# Pyr0-Piezo_Direct-Extruder-FFC-Breakout_.net
KiCad netlist of a schematic drawn in EAGLE
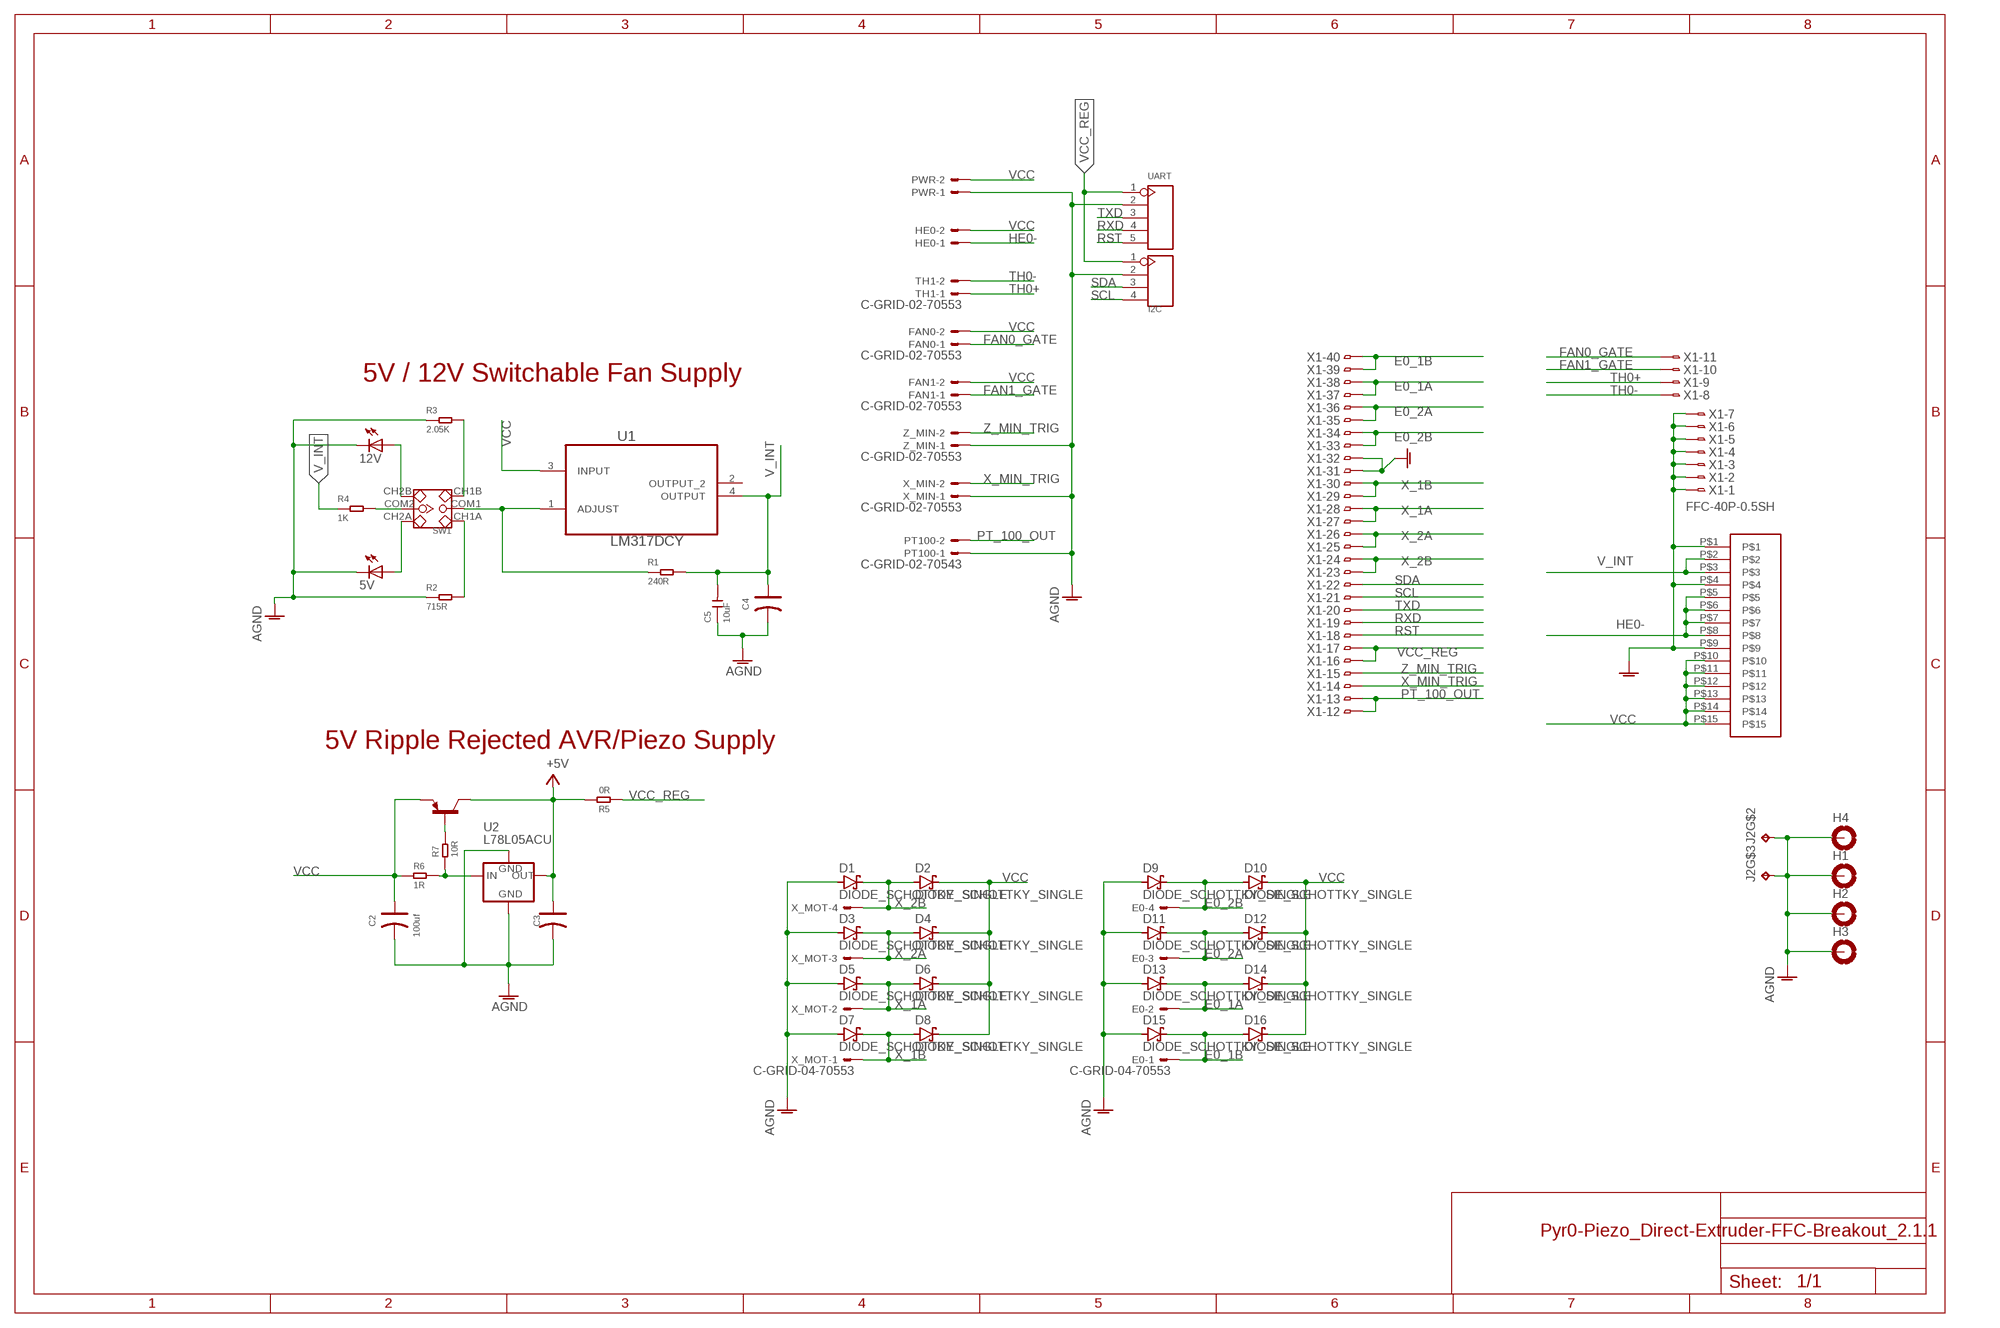
[diagram p0: schematic, sheet 1]

(export (version "E")
  (design (tool "Eeschema 10.0.6"))
  (components
    (comp (ref "5V")
      (value "LEDCHIP-LED0805")
      (footprint "eagle-import:CHIP-LED0805")
      (libsource (lib "eagle-import") (part "LEDCHIP-LED0805"))
    )
    (comp (ref "12V")
      (value "LEDCHIP-LED0805")
      (footprint "eagle-import:CHIP-LED0805")
      (libsource (lib "eagle-import") (part "LEDCHIP-LED0805"))
    )
    (comp (ref "C2")
      (value "100uf")
      (footprint "eagle-import:ALU-C-D5.3MM_LEFT")
      (fields (field (name "MPN") "KS 100uF/16V"))
      (libsource (lib "eagle-import") (part "DIP-ALUMINUM-100UF-16V(D5-H7MM)LEFT"))
    )
    (comp (ref "C3")
      (value "100uf")
      (footprint "eagle-import:ALU-C-D5.3MM_RIGHT")
      (libsource (lib "eagle-import") (part "DIP-ALUMINUM-100UF-16V(D5-H7MM)RIGHT"))
    )
    (comp (ref "C4")
      (value "100uf")
      (footprint "eagle-import:ALU-C-D5.3MM_RIGHT")
      (libsource (lib "eagle-import") (part "DIP-ALUMINUM-100UF-16V(D5-H7MM)RIGHT"))
    )
    (comp (ref "C5")
      (value "10uF")
      (footprint "eagle-import:CAPC2012X130")
      (libsource (lib "eagle-import") (part "SEEED-CAPACITOR_CERAMIC-10UF-25V-10%-X5R(0805)CAP_0805-3D"))
    )
    (comp (ref "D1")
      (value "DIODE_SCHOTTKY_SINGLE")
      (footprint "eagle-import:DO-214AC")
      (libsource (lib "eagle-import") (part "DIODE_SCHOTTKY_SINGLE"))
    )
    (comp (ref "D2")
      (value "DIODE_SCHOTTKY_SINGLE")
      (footprint "eagle-import:DO-214AC")
      (libsource (lib "eagle-import") (part "DIODE_SCHOTTKY_SINGLE"))
    )
    (comp (ref "D3")
      (value "DIODE_SCHOTTKY_SINGLE")
      (footprint "eagle-import:DO-214AC")
      (libsource (lib "eagle-import") (part "DIODE_SCHOTTKY_SINGLE"))
    )
    (comp (ref "D4")
      (value "DIODE_SCHOTTKY_SINGLE")
      (footprint "eagle-import:DO-214AC")
      (libsource (lib "eagle-import") (part "DIODE_SCHOTTKY_SINGLE"))
    )
    (comp (ref "D5")
      (value "DIODE_SCHOTTKY_SINGLE")
      (footprint "eagle-import:DO-214AC")
      (libsource (lib "eagle-import") (part "DIODE_SCHOTTKY_SINGLE"))
    )
    (comp (ref "D6")
      (value "DIODE_SCHOTTKY_SINGLE")
      (footprint "eagle-import:DO-214AC")
      (libsource (lib "eagle-import") (part "DIODE_SCHOTTKY_SINGLE"))
    )
    (comp (ref "D7")
      (value "DIODE_SCHOTTKY_SINGLE")
      (footprint "eagle-import:DO-214AC")
      (libsource (lib "eagle-import") (part "DIODE_SCHOTTKY_SINGLE"))
    )
    (comp (ref "D8")
      (value "DIODE_SCHOTTKY_SINGLE")
      (footprint "eagle-import:DO-214AC")
      (libsource (lib "eagle-import") (part "DIODE_SCHOTTKY_SINGLE"))
    )
    (comp (ref "D9")
      (value "DIODE_SCHOTTKY_SINGLE")
      (footprint "eagle-import:DO-214AC")
      (libsource (lib "eagle-import") (part "DIODE_SCHOTTKY_SINGLE"))
    )
    (comp (ref "D10")
      (value "DIODE_SCHOTTKY_SINGLE")
      (footprint "eagle-import:DO-214AC")
      (libsource (lib "eagle-import") (part "DIODE_SCHOTTKY_SINGLE"))
    )
    (comp (ref "D11")
      (value "DIODE_SCHOTTKY_SINGLE")
      (footprint "eagle-import:DO-214AC")
      (libsource (lib "eagle-import") (part "DIODE_SCHOTTKY_SINGLE"))
    )
    (comp (ref "D12")
      (value "DIODE_SCHOTTKY_SINGLE")
      (footprint "eagle-import:DO-214AC")
      (libsource (lib "eagle-import") (part "DIODE_SCHOTTKY_SINGLE"))
    )
    (comp (ref "D13")
      (value "DIODE_SCHOTTKY_SINGLE")
      (footprint "eagle-import:DO-214AC")
      (libsource (lib "eagle-import") (part "DIODE_SCHOTTKY_SINGLE"))
    )
    (comp (ref "D14")
      (value "DIODE_SCHOTTKY_SINGLE")
      (footprint "eagle-import:DO-214AC")
      (libsource (lib "eagle-import") (part "DIODE_SCHOTTKY_SINGLE"))
    )
    (comp (ref "D15")
      (value "DIODE_SCHOTTKY_SINGLE")
      (footprint "eagle-import:DO-214AC")
      (libsource (lib "eagle-import") (part "DIODE_SCHOTTKY_SINGLE"))
    )
    (comp (ref "D16")
      (value "DIODE_SCHOTTKY_SINGLE")
      (footprint "eagle-import:DO-214AC")
      (libsource (lib "eagle-import") (part "DIODE_SCHOTTKY_SINGLE"))
    )
    (comp (ref "E0")
      (value "C-GRID-04-70553")
      (footprint "eagle-import:70553-04")
      (fields (field (name "MF") "MOLEX"))
      (libsource (lib "eagle-import") (part "C-GRID-04-70553"))
    )
    (comp (ref "FAN0")
      (value "C-GRID-02-70553")
      (footprint "eagle-import:70553-02")
      (fields (field (name "MF") "MOLEX"))
      (libsource (lib "eagle-import") (part "C-GRID-02-70553"))
    )
    (comp (ref "FAN1")
      (value "C-GRID-02-70553")
      (footprint "eagle-import:70553-02")
      (fields (field (name "MF") "MOLEX"))
      (libsource (lib "eagle-import") (part "C-GRID-02-70553"))
    )
    (comp (ref "H1")
      (value "HOLES_MOUNT-PAD-ROUND3.2")
      (footprint "eagle-import:HOLES_3,2-PAD")
      (libsource (lib "eagle-import") (part "HOLES_MOUNT-PAD-ROUND3.2"))
    )
    (comp (ref "H2")
      (value "HOLES_MOUNT-PAD-ROUND3.2")
      (footprint "eagle-import:HOLES_3,2-PAD")
      (libsource (lib "eagle-import") (part "HOLES_MOUNT-PAD-ROUND3.2"))
    )
    (comp (ref "H3")
      (value "HOLES_MOUNT-PAD-ROUND3.2")
      (footprint "eagle-import:HOLES_3,2-PAD")
      (libsource (lib "eagle-import") (part "HOLES_MOUNT-PAD-ROUND3.2"))
    )
    (comp (ref "H4")
      (value "HOLES_MOUNT-PAD-ROUND3.2")
      (footprint "eagle-import:HOLES_3,2-PAD")
      (libsource (lib "eagle-import") (part "HOLES_MOUNT-PAD-ROUND3.2"))
    )
    (comp (ref "HE0")
      (value "KK-156-2")
      (footprint "eagle-import:KK-156-2")
      (fields (field (name "MF") "MOLEX"))
      (libsource (lib "eagle-import") (part "KK-156-2"))
    )
    (comp (ref "I2C")
      (value "SEEED-CONNECTOR_DIP-BLACK-FEMALE-HEADER-VERT(4P-2.54)JST-2.54MM_4P")
      (footprint "eagle-import:HDRVR4W64P254_1X4_1016X254X575B")
      (libsource (lib "eagle-import") (part "SEEED-CONNECTOR_DIP-BLACK-FEMALE-HEADER-VERT(4P-2.54)JST-2.54MM_4P"))
    )
    (comp (ref "J2")
      (value "FFC-15P-1MM")
      (footprint "eagle-import:FFC-15P-1MM")
      (libsource (lib "eagle-import") (part "FFC-15P-1MM"))
    )
    (comp (ref "PT100")
      (value "C-GRID-02-70543")
      (footprint "eagle-import:70543-02")
      (fields (field (name "MF") "MOLEX"))
      (libsource (lib "eagle-import") (part "C-GRID-02-70543"))
    )
    (comp (ref "PWR")
      (value "KK-156-2")
      (footprint "eagle-import:KK-156-2")
      (fields (field (name "MF") "MOLEX"))
      (libsource (lib "eagle-import") (part "KK-156-2"))
    )
    (comp (ref "Q2")
      (value "MMBT2907ALT1-PNP-SOT23-BEC")
      (footprint "eagle-import:SOT23-BEC")
      (libsource (lib "eagle-import") (part "-PNP-SOT23-BECMMBT2907ALT1"))
    )
    (comp (ref "R1")
      (value "240R")
      (footprint "eagle-import:SEEED-RESISTOR_R0603")
      (libsource (lib "eagle-import") (part "SEEED-RESISTOR_SMD-RES-1.5K-1%-1/10W(0603)DETAILED_MODEL"))
    )
    (comp (ref "R2")
      (value "715R")
      (footprint "eagle-import:SEEED-RESISTOR_R0603")
      (libsource (lib "eagle-import") (part "SEEED-RESISTOR_SMD-RES-1.5K-1%-1/10W(0603)DETAILED_MODEL"))
    )
    (comp (ref "R3")
      (value "2.05K")
      (footprint "eagle-import:SEEED-RESISTOR_R0603")
      (libsource (lib "eagle-import") (part "SEEED-RESISTOR_SMD-RES-1.5K-1%-1/10W(0603)DETAILED_MODEL"))
    )
    (comp (ref "R4")
      (value "1K")
      (footprint "eagle-import:SEEED-RESISTOR_R0603")
      (libsource (lib "eagle-import") (part "SEEED-RESISTOR_SMD-RES-1.5K-1%-1/10W(0603)DETAILED_MODEL"))
    )
    (comp (ref "R5")
      (value "0R")
      (footprint "eagle-import:R0805")
      (fields (field (name "MPN") "RC0805JR-072KL"))
      (libsource (lib "eagle-import") (part "SMD-RES-2K-5%-1/8W(0805)"))
    )
    (comp (ref "R6")
      (value "1R")
      (footprint "eagle-import:R0805")
      (fields (field (name "MPN") "RC0805JR-072KL"))
      (libsource (lib "eagle-import") (part "SMD-RES-2K-5%-1/8W(0805)"))
    )
    (comp (ref "R7")
      (value "10R")
      (footprint "eagle-import:R0805")
      (fields (field (name "MPN") "RC0805JR-072KL"))
      (libsource (lib "eagle-import") (part "SMD-RES-2K-5%-1/8W(0805)"))
    )
    (comp (ref "SW1")
      (value "SEEED-SWITCH_DIP-TOGGLE-SWITCH-2CH-(2X3P-2.54)DPDT_254_6P_UPDATE")
      (footprint "eagle-import:SEEED-SWITCH_SW6-2.54-9.0X3.5X3.2+2.0MM")
      (libsource (lib "eagle-import") (part "SEEED-SWITCH_DIP-TOGGLE-SWITCH-2CH-(2X3P-2.54)DPDT_254_6P_UPDATE"))
    )
    (comp (ref "TH1")
      (value "C-GRID-02-70553")
      (footprint "eagle-import:70553-02")
      (fields (field (name "MF") "MOLEX"))
      (libsource (lib "eagle-import") (part "C-GRID-02-70553"))
    )
    (comp (ref "U1")
      (value "LM317DCY")
      (footprint "eagle-import:SOT230P700X180-4N")
      (fields (field (name "MF") "Texas Instruments"))
      (libsource (lib "eagle-import") (part "LM317DCY"))
    )
    (comp (ref "U2")
      (value "L78L05ACU")
      (footprint "eagle-import:SOT89")
      (fields (field (name "MF") "STMicroelectronics") (field (name "MP") "L78L05ACU-TR"))
      (libsource (lib "eagle-import") (part "L78L05ACU"))
    )
    (comp (ref "UART")
      (value "JST-2.54MM_5P-2.54JST_2.54MM_5P_F")
      (footprint "eagle-import:HDRVR5W64P254_1X5_1270X254X575B")
      (libsource (lib "eagle-import") (part "JST-2.54MM_5P-2.54JST_2.54MM_5P_F"))
    )
    (comp (ref "X1")
      (value "FFC-40P-0.5SH")
      (footprint "eagle-import:FH12-40S-0.5SH")
      (fields (field (name "MPN") "FH12-40S-0.5SH(55)"))
      (libsource (lib "eagle-import") (part "FFC-40P-0.5SH"))
    )
    (comp (ref "X_MIN")
      (value "C-GRID-02-70553")
      (footprint "eagle-import:70553-02")
      (fields (field (name "MF") "MOLEX"))
      (libsource (lib "eagle-import") (part "C-GRID-02-70553"))
    )
    (comp (ref "X_MOT")
      (value "C-GRID-04-70553")
      (footprint "eagle-import:70553-04")
      (fields (field (name "MF") "MOLEX"))
      (libsource (lib "eagle-import") (part "C-GRID-04-70553"))
    )
    (comp (ref "Z_MIN")
      (value "C-GRID-02-70553")
      (footprint "eagle-import:70553-02")
      (fields (field (name "MF") "MOLEX"))
      (libsource (lib "eagle-import") (part "C-GRID-02-70553"))
    )
  )
  (nets
    (net (code "1") (name "+5V") (class "Default")
      (node (ref "C3") (pin "+") (pinfunction "+_+") (pintype "passive"))
      (node (ref "Q2") (pin "C") (pinfunction "C_C") (pintype "passive"))
      (node (ref "R5") (pin "2") (pinfunction "2_2") (pintype "passive"))
      (node (ref "U2") (pin "1") (pinfunction "OUT_1") (pintype "output"))
    )
    (net (code "2") (name "/E0_1A") (class "Default")
      (node (ref "D13") (pin "C") (pinfunction "C_C") (pintype "passive"))
      (node (ref "D14") (pin "A") (pinfunction "A_A") (pintype "passive"))
      (node (ref "E0") (pin "2") (pinfunction "S_2") (pintype "passive"))
      (node (ref "X1") (pin "37") (pinfunction "1_37") (pintype "passive"))
      (node (ref "X1") (pin "38") (pinfunction "1_38") (pintype "passive"))
    )
    (net (code "3") (name "/E0_1B") (class "Default")
      (node (ref "D15") (pin "C") (pinfunction "C_C") (pintype "passive"))
      (node (ref "D16") (pin "A") (pinfunction "A_A") (pintype "passive"))
      (node (ref "E0") (pin "1") (pinfunction "S_1") (pintype "passive"))
      (node (ref "X1") (pin "39") (pinfunction "1_39") (pintype "passive"))
      (node (ref "X1") (pin "40") (pinfunction "1_40") (pintype "passive"))
    )
    (net (code "4") (name "/E0_2A") (class "Default")
      (node (ref "D11") (pin "C") (pinfunction "C_C") (pintype "passive"))
      (node (ref "D12") (pin "A") (pinfunction "A_A") (pintype "passive"))
      (node (ref "E0") (pin "3") (pinfunction "S_3") (pintype "passive"))
      (node (ref "X1") (pin "35") (pinfunction "1_35") (pintype "passive"))
      (node (ref "X1") (pin "36") (pinfunction "1_36") (pintype "passive"))
    )
    (net (code "5") (name "/E0_2B") (class "Default")
      (node (ref "D10") (pin "A") (pinfunction "A_A") (pintype "passive"))
      (node (ref "D9") (pin "C") (pinfunction "C_C") (pintype "passive"))
      (node (ref "E0") (pin "4") (pinfunction "S_4") (pintype "passive"))
      (node (ref "X1") (pin "33") (pinfunction "1_33") (pintype "passive"))
      (node (ref "X1") (pin "34") (pinfunction "1_34") (pintype "passive"))
    )
    (net (code "6") (name "/FAN0_GATE") (class "Default")
      (node (ref "FAN0") (pin "1") (pinfunction "S_1") (pintype "passive"))
      (node (ref "X1") (pin "11") (pinfunction "1_11") (pintype "passive"))
    )
    (net (code "7") (name "/FAN1_GATE") (class "Default")
      (node (ref "FAN1") (pin "1") (pinfunction "S_1") (pintype "passive"))
      (node (ref "X1") (pin "10") (pinfunction "1_10") (pintype "passive"))
    )
    (net (code "8") (name "/HE0-") (class "Default")
      (node (ref "HE0") (pin "1") (pinfunction "S_1") (pintype "passive"))
      (node (ref "J2") (pin "P$5") (pinfunction "P$5_P$5") (pintype "bidirectional"))
      (node (ref "J2") (pin "P$6") (pinfunction "P$6_P$6") (pintype "bidirectional"))
      (node (ref "J2") (pin "P$7") (pinfunction "P$7_P$7") (pintype "bidirectional"))
      (node (ref "J2") (pin "P$8") (pinfunction "P$8_P$8") (pintype "bidirectional"))
    )
    (net (code "9") (name "/PT_100_OUT") (class "Default")
      (node (ref "PT100") (pin "2") (pinfunction "S_2") (pintype "passive"))
      (node (ref "X1") (pin "12") (pinfunction "1_12") (pintype "passive"))
      (node (ref "X1") (pin "13") (pinfunction "1_13") (pintype "passive"))
    )
    (net (code "10") (name "/RST") (class "Default")
      (node (ref "UART") (pin "5") (pinfunction "P$5_5") (pintype "bidirectional"))
      (node (ref "X1") (pin "18") (pinfunction "1_18") (pintype "passive"))
    )
    (net (code "11") (name "/RXD") (class "Default")
      (node (ref "UART") (pin "4") (pinfunction "P$4_4") (pintype "bidirectional"))
      (node (ref "X1") (pin "19") (pinfunction "1_19") (pintype "passive"))
    )
    (net (code "12") (name "/SCL") (class "Default")
      (node (ref "I2C") (pin "4") (pinfunction "P$4_4") (pintype "bidirectional"))
      (node (ref "X1") (pin "21") (pinfunction "1_21") (pintype "passive"))
    )
    (net (code "13") (name "/SDA") (class "Default")
      (node (ref "I2C") (pin "3") (pinfunction "P$3_3") (pintype "bidirectional"))
      (node (ref "X1") (pin "22") (pinfunction "1_22") (pintype "passive"))
    )
    (net (code "14") (name "/TH0+") (class "Default")
      (node (ref "TH1") (pin "1") (pinfunction "S_1") (pintype "passive"))
      (node (ref "X1") (pin "9") (pinfunction "1_9") (pintype "passive"))
    )
    (net (code "15") (name "/TH0-") (class "Default")
      (node (ref "TH1") (pin "2") (pinfunction "S_2") (pintype "passive"))
      (node (ref "X1") (pin "8") (pinfunction "1_8") (pintype "passive"))
    )
    (net (code "16") (name "/TXD") (class "Default")
      (node (ref "UART") (pin "3") (pinfunction "P$3_3") (pintype "bidirectional"))
      (node (ref "X1") (pin "20") (pinfunction "1_20") (pintype "passive"))
    )
    (net (code "17") (name "/VCC") (class "Default")
      (node (ref "C2") (pin "+") (pinfunction "+_+") (pintype "passive"))
      (node (ref "D10") (pin "C") (pinfunction "C_C") (pintype "passive"))
      (node (ref "D12") (pin "C") (pinfunction "C_C") (pintype "passive"))
      (node (ref "D14") (pin "C") (pinfunction "C_C") (pintype "passive"))
      (node (ref "D16") (pin "C") (pinfunction "C_C") (pintype "passive"))
      (node (ref "D2") (pin "C") (pinfunction "C_C") (pintype "passive"))
      (node (ref "D4") (pin "C") (pinfunction "C_C") (pintype "passive"))
      (node (ref "D6") (pin "C") (pinfunction "C_C") (pintype "passive"))
      (node (ref "D8") (pin "C") (pinfunction "C_C") (pintype "passive"))
      (node (ref "FAN0") (pin "2") (pinfunction "S_2") (pintype "passive"))
      (node (ref "FAN1") (pin "2") (pinfunction "S_2") (pintype "passive"))
      (node (ref "HE0") (pin "2") (pinfunction "S_2") (pintype "passive"))
      (node (ref "J2") (pin "P$10") (pinfunction "P$10_P$10") (pintype "bidirectional"))
      (node (ref "J2") (pin "P$11") (pinfunction "P$11_P$11") (pintype "bidirectional"))
      (node (ref "J2") (pin "P$12") (pinfunction "P$12_P$12") (pintype "bidirectional"))
      (node (ref "J2") (pin "P$13") (pinfunction "P$13_P$13") (pintype "bidirectional"))
      (node (ref "J2") (pin "P$14") (pinfunction "P$14_P$14") (pintype "bidirectional"))
      (node (ref "J2") (pin "P$15") (pinfunction "P$15_P$15") (pintype "bidirectional"))
      (node (ref "PWR") (pin "2") (pinfunction "S_2") (pintype "passive"))
      (node (ref "Q2") (pin "E") (pinfunction "E_E") (pintype "passive"))
      (node (ref "R6") (pin "1") (pinfunction "1_1") (pintype "passive"))
      (node (ref "U1") (pin "3") (pinfunction "INPUT_3") (pintype "input"))
    )
    (net (code "18") (name "/X_1A") (class "Default")
      (node (ref "D5") (pin "C") (pinfunction "C_C") (pintype "passive"))
      (node (ref "D6") (pin "A") (pinfunction "A_A") (pintype "passive"))
      (node (ref "X1") (pin "27") (pinfunction "1_27") (pintype "passive"))
      (node (ref "X1") (pin "28") (pinfunction "1_28") (pintype "passive"))
      (node (ref "X_MOT") (pin "2") (pinfunction "S_2") (pintype "passive"))
    )
    (net (code "19") (name "/X_1B") (class "Default")
      (node (ref "D7") (pin "C") (pinfunction "C_C") (pintype "passive"))
      (node (ref "D8") (pin "A") (pinfunction "A_A") (pintype "passive"))
      (node (ref "X1") (pin "29") (pinfunction "1_29") (pintype "passive"))
      (node (ref "X1") (pin "30") (pinfunction "1_30") (pintype "passive"))
      (node (ref "X_MOT") (pin "1") (pinfunction "S_1") (pintype "passive"))
    )
    (net (code "20") (name "/X_2A") (class "Default")
      (node (ref "D3") (pin "C") (pinfunction "C_C") (pintype "passive"))
      (node (ref "D4") (pin "A") (pinfunction "A_A") (pintype "passive"))
      (node (ref "X1") (pin "25") (pinfunction "1_25") (pintype "passive"))
      (node (ref "X1") (pin "26") (pinfunction "1_26") (pintype "passive"))
      (node (ref "X_MOT") (pin "3") (pinfunction "S_3") (pintype "passive"))
    )
    (net (code "21") (name "/X_2B") (class "Default")
      (node (ref "D1") (pin "C") (pinfunction "C_C") (pintype "passive"))
      (node (ref "D2") (pin "A") (pinfunction "A_A") (pintype "passive"))
      (node (ref "X1") (pin "23") (pinfunction "1_23") (pintype "passive"))
      (node (ref "X1") (pin "24") (pinfunction "1_24") (pintype "passive"))
      (node (ref "X_MOT") (pin "4") (pinfunction "S_4") (pintype "passive"))
    )
    (net (code "22") (name "/X_MIN_TRIG") (class "Default")
      (node (ref "X1") (pin "14") (pinfunction "1_14") (pintype "passive"))
      (node (ref "X_MIN") (pin "2") (pinfunction "S_2") (pintype "passive"))
    )
    (net (code "23") (name "/Z_MIN_TRIG") (class "Default")
      (node (ref "X1") (pin "15") (pinfunction "1_15") (pintype "passive"))
      (node (ref "Z_MIN") (pin "2") (pinfunction "S_2") (pintype "passive"))
    )
    (net (code "24") (name "AGND") (class "Default")
      (node (ref "12V") (pin "C") (pinfunction "C_C") (pintype "passive"))
      (node (ref "5V") (pin "C") (pinfunction "C_C") (pintype "passive"))
      (node (ref "C2") (pin "-") (pinfunction "-_-") (pintype "passive"))
      (node (ref "C3") (pin "-") (pinfunction "-_-") (pintype "passive"))
      (node (ref "C4") (pin "-") (pinfunction "-_-") (pintype "passive"))
      (node (ref "C5") (pin "1") (pinfunction "1_1") (pintype "passive"))
      (node (ref "D1") (pin "A") (pinfunction "A_A") (pintype "passive"))
      (node (ref "D11") (pin "A") (pinfunction "A_A") (pintype "passive"))
      (node (ref "D13") (pin "A") (pinfunction "A_A") (pintype "passive"))
      (node (ref "D15") (pin "A") (pinfunction "A_A") (pintype "passive"))
      (node (ref "D3") (pin "A") (pinfunction "A_A") (pintype "passive"))
      (node (ref "D5") (pin "A") (pinfunction "A_A") (pintype "passive"))
      (node (ref "D7") (pin "A") (pinfunction "A_A") (pintype "passive"))
      (node (ref "D9") (pin "A") (pinfunction "A_A") (pintype "passive"))
      (node (ref "H1") (pin "B3,2") (pinfunction "MOUNT_B3,2") (pintype "passive"))
      (node (ref "H2") (pin "B3,2") (pinfunction "MOUNT_B3,2") (pintype "passive"))
      (node (ref "H3") (pin "B3,2") (pinfunction "MOUNT_B3,2") (pintype "passive"))
      (node (ref "H4") (pin "B3,2") (pinfunction "MOUNT_B3,2") (pintype "passive"))
      (node (ref "I2C") (pin "2") (pinfunction "P$2_2") (pintype "bidirectional"))
      (node (ref "J2") (pin "P$1") (pinfunction "P$1_P$1") (pintype "bidirectional"))
      (node (ref "J2") (pin "P$16") (pinfunction "TP_P$16") (pintype "input"))
      (node (ref "J2") (pin "P$17") (pinfunction "TP_P$17") (pintype "input"))
      (node (ref "J2") (pin "P$4") (pinfunction "P$4_P$4") (pintype "bidirectional"))
      (node (ref "J2") (pin "P$9") (pinfunction "P$9_P$9") (pintype "bidirectional"))
      (node (ref "PT100") (pin "1") (pinfunction "S_1") (pintype "passive"))
      (node (ref "PWR") (pin "1") (pinfunction "S_1") (pintype "passive"))
      (node (ref "R2") (pin "1") (pinfunction "1_1") (pintype "passive"))
      (node (ref "R3") (pin "1") (pinfunction "1_1") (pintype "passive"))
      (node (ref "U2") (pin "2") (pinfunction "GND_2") (pintype "power_in"))
      (node (ref "U2") (pin "PAD") (pinfunction "PAD_PAD") (pintype "power_in"))
      (node (ref "UART") (pin "2") (pinfunction "P$2_2") (pintype "bidirectional"))
      (node (ref "X1") (pin "1") (pinfunction "1_1") (pintype "passive"))
      (node (ref "X1") (pin "2") (pinfunction "1_2") (pintype "passive"))
      (node (ref "X1") (pin "3") (pinfunction "1_3") (pintype "passive"))
      (node (ref "X1") (pin "31") (pinfunction "1_31") (pintype "passive"))
      (node (ref "X1") (pin "32") (pinfunction "1_32") (pintype "passive"))
      (node (ref "X1") (pin "4") (pinfunction "1_4") (pintype "passive"))
      (node (ref "X1") (pin "5") (pinfunction "1_5") (pintype "passive"))
      (node (ref "X1") (pin "6") (pinfunction "1_6") (pintype "passive"))
      (node (ref "X1") (pin "7") (pinfunction "1_7") (pintype "passive"))
      (node (ref "X_MIN") (pin "1") (pinfunction "S_1") (pintype "passive"))
      (node (ref "Z_MIN") (pin "1") (pinfunction "S_1") (pintype "passive"))
    )
    (net (code "25") (name "Net-(5V-PadA)") (class "Default")
      (node (ref "5V") (pin "A") (pinfunction "A_A") (pintype "passive"))
      (node (ref "SW1") (pin "CH2A") (pinfunction "CH2A_CH2A") (pintype "bidirectional"))
    )
    (net (code "26") (name "Net-(12V-PadA)") (class "Default")
      (node (ref "12V") (pin "A") (pinfunction "A_A") (pintype "passive"))
      (node (ref "SW1") (pin "CH2B") (pinfunction "CH2B_CH2B") (pintype "bidirectional"))
    )
    (net (code "27") (name "Net-(Q2-PadB)") (class "Default")
      (node (ref "Q2") (pin "B") (pinfunction "B_B") (pintype "passive"))
      (node (ref "R7") (pin "2") (pinfunction "2_2") (pintype "passive"))
    )
    (net (code "28") (name "Net-(R2-Pad2)") (class "Default")
      (node (ref "R2") (pin "2") (pinfunction "2_2") (pintype "passive"))
      (node (ref "SW1") (pin "CH1A") (pinfunction "CH1A_CH1A") (pintype "bidirectional"))
    )
    (net (code "29") (name "Net-(R3-Pad2)") (class "Default")
      (node (ref "R3") (pin "2") (pinfunction "2_2") (pintype "passive"))
      (node (ref "SW1") (pin "CH1B") (pinfunction "CH1B_CH1B") (pintype "bidirectional"))
    )
    (net (code "30") (name "Net-(R4-Pad2)") (class "Default")
      (node (ref "R4") (pin "2") (pinfunction "2_2") (pintype "passive"))
      (node (ref "SW1") (pin "COM2") (pinfunction "COM2_COM2") (pintype "bidirectional"))
    )
    (net (code "31") (name "Net-(U1-ADJUST)") (class "Default")
      (node (ref "R1") (pin "1") (pinfunction "1_1") (pintype "passive"))
      (node (ref "SW1") (pin "COM1") (pinfunction "COM1_COM1") (pintype "bidirectional"))
      (node (ref "U1") (pin "1") (pinfunction "ADJUST_1") (pintype "input"))
    )
    (net (code "32") (name "Net-(U2-IN)") (class "Default")
      (node (ref "R6") (pin "2") (pinfunction "2_2") (pintype "passive"))
      (node (ref "R7") (pin "1") (pinfunction "1_1") (pintype "passive"))
      (node (ref "U2") (pin "3") (pinfunction "IN_3") (pintype "input"))
    )
    (net (code "33") (name "VCC_REG") (class "Default")
      (node (ref "I2C") (pin "1") (pinfunction "P$1_1") (pintype "bidirectional"))
      (node (ref "R5") (pin "1") (pinfunction "1_1") (pintype "passive"))
      (node (ref "UART") (pin "1") (pinfunction "P$1_1") (pintype "bidirectional"))
      (node (ref "X1") (pin "16") (pinfunction "1_16") (pintype "passive"))
      (node (ref "X1") (pin "17") (pinfunction "1_17") (pintype "passive"))
    )
    (net (code "34") (name "V_INT") (class "Default")
      (node (ref "C4") (pin "+") (pinfunction "+_+") (pintype "passive"))
      (node (ref "C5") (pin "2") (pinfunction "2_2") (pintype "passive"))
      (node (ref "J2") (pin "P$2") (pinfunction "P$2_P$2") (pintype "bidirectional"))
      (node (ref "J2") (pin "P$3") (pinfunction "P$3_P$3") (pintype "bidirectional"))
      (node (ref "R1") (pin "2") (pinfunction "2_2") (pintype "passive"))
      (node (ref "R4") (pin "1") (pinfunction "1_1") (pintype "passive"))
      (node (ref "U1") (pin "4") (pinfunction "OUTPUT_4") (pintype "output"))
    )
    (net (code "35") (name "unconnected-(U1-OUTPUT_2-Pad2)") (class "Default")
      (node (ref "U1") (pin "2") (pinfunction "OUTPUT_2_2") (pintype "output"))
    )
  )
)
